# automatic_temp_control.net
KiCad netlist of a schematic drawn in EAGLE
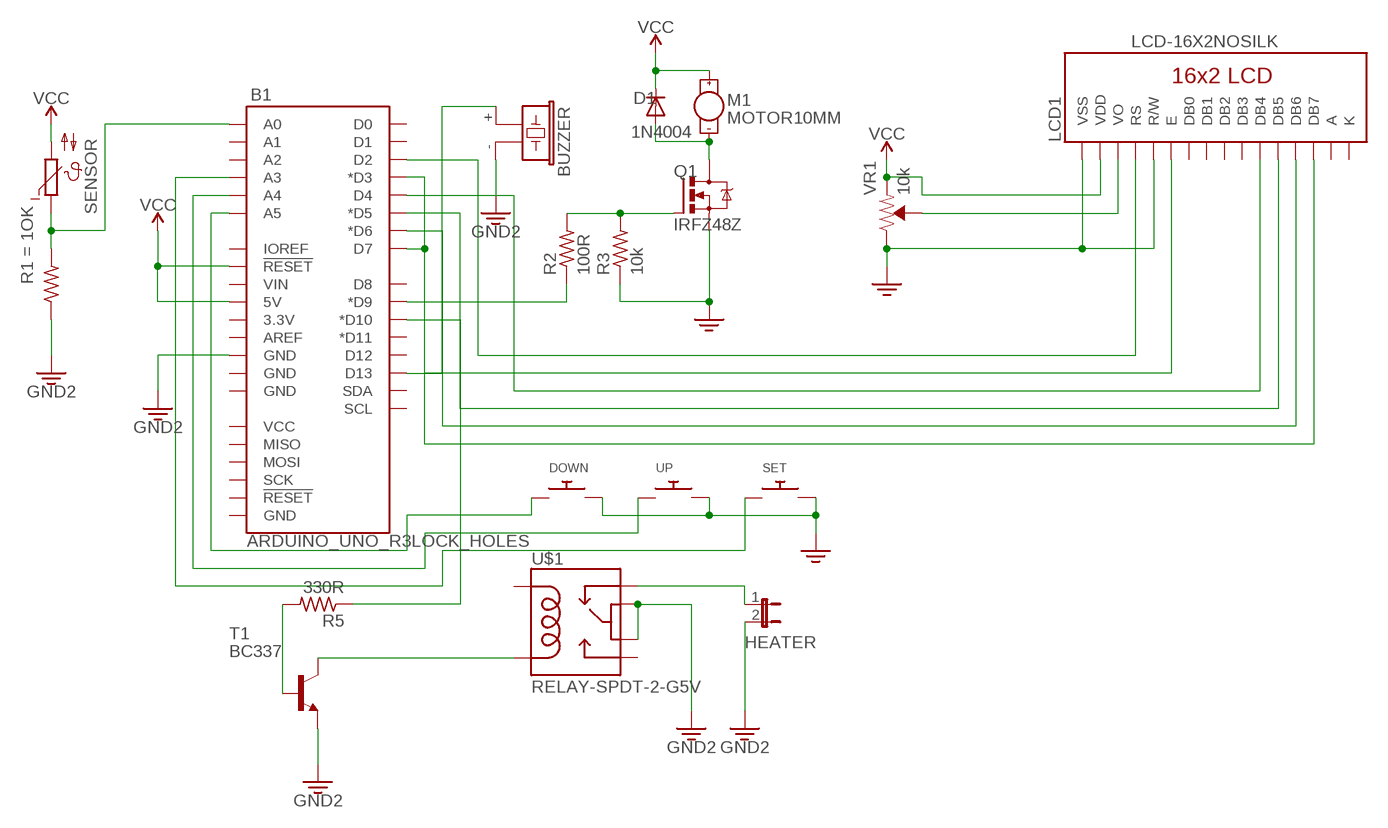
[diagram p0: schematic, sheet 1]

(export (version "E")
  (design (tool "Eeschema 10.0.6"))
  (components
    (comp (ref "B1")
      (value "ARDUINO_UNO_R3LOCK_HOLES")
      (footprint "eagle-import:ARDUINO_R3_LOCK_HOLES")
      (libsource (lib "eagle-import") (part "ARDUINO_UNO_R3LOCK_HOLES"))
    )
    (comp (ref "BUZZER")
      (value "F/CM04P")
      (footprint "eagle-import:F_CM04P")
      (libsource (lib "eagle-import") (part "F/CM04P"))
    )
    (comp (ref "D1")
      (value "1N4004")
      (footprint "eagle-import:DO41-10")
      (libsource (lib "eagle-import") (part "1N4004"))
    )
    (comp (ref "DOWN")
      (value "SWITCH_PUSHBUTTONEVQ-PE")
      (footprint "eagle-import:TACT_PANA-EVQ")
      (libsource (lib "eagle-import") (part "SWITCH_PUSHBUTTONEVQ-PE"))
    )
    (comp (ref "HEATER")
      (value "JP1E")
      (footprint "eagle-import:JP1")
      (libsource (lib "eagle-import") (part "JP1E"))
    )
    (comp (ref "LCD1")
      (value "LCD-16X2NOSILK")
      (footprint "eagle-import:LCD-16X2_NOSILK")
      (libsource (lib "eagle-import") (part "LCD-16X2NOSILK"))
    )
    (comp (ref "M1")
      (value "MOTOR10MM")
      (footprint "eagle-import:VIBE-MOTOR-10MM")
      (libsource (lib "eagle-import") (part "MOTOR10MM"))
    )
    (comp (ref "Q1")
      (value "IRFZ48Z")
      (footprint "eagle-import:TO220BH")
      (libsource (lib "eagle-import") (part "IRFZ48Z"))
    )
    (comp (ref "R2")
      (value "100R")
      (footprint "eagle-import:0204_7")
      (libsource (lib "eagle-import") (part "R-US_0204/7"))
    )
    (comp (ref "R3")
      (value "10k")
      (footprint "eagle-import:0204_7")
      (libsource (lib "eagle-import") (part "R-US_0204/7"))
    )
    (comp (ref "R4")
      (value "R-US_0204/7")
      (footprint "eagle-import:0204_7")
      (fields (field (name "R1") "1OK"))
      (libsource (lib "eagle-import") (part "R-US_0204/7"))
    )
    (comp (ref "R5")
      (value "330R")
      (footprint "eagle-import:0204_7")
      (libsource (lib "eagle-import") (part "R-US_0204/7"))
    )
    (comp (ref "SENSOR")
      (value "NTC640-9")
      (footprint "eagle-import:N640")
      (libsource (lib "eagle-import") (part "NTC640-9"))
    )
    (comp (ref "SET")
      (value "SWITCH_PUSHBUTTONEVQ-PE")
      (footprint "eagle-import:TACT_PANA-EVQ")
      (libsource (lib "eagle-import") (part "SWITCH_PUSHBUTTONEVQ-PE"))
    )
    (comp (ref "T1")
      (value "BC337")
      (footprint "eagle-import:TO92")
      (libsource (lib "eagle-import") (part "BC337"))
    )
    (comp (ref "U$1")
      (value "RELAY-SPDT-2-G5V")
      (footprint "eagle-import:RELAY-G5V")
      (libsource (lib "eagle-import") (part "RELAY-SPDT-2-G5V"))
    )
    (comp (ref "UP")
      (value "SWITCH_PUSHBUTTONEVQ-PE")
      (footprint "eagle-import:TACT_PANA-EVQ")
      (libsource (lib "eagle-import") (part "SWITCH_PUSHBUTTONEVQ-PE"))
    )
    (comp (ref "VR1")
      (value "10k")
      (footprint "eagle-import:TRIMPOT-PTH-3386U")
      (libsource (lib "eagle-import") (part "TRIMPOT-PTH-10MM-KNOB-1/2W-10%"))
    )
  )
  (nets
    (net (code "1") (name "/A") (class "Default")
      (node (ref "LCD1") (pin "15") (pinfunction "A_15") (pintype "power_in"))
    )
    (net (code "2") (name "/K") (class "Default")
      (node (ref "LCD1") (pin "16") (pinfunction "K_16") (pintype "power_in"))
    )
    (net (code "3") (name "GND2") (class "Default")
      (node (ref "B1") (pin "GND@4") (pinfunction "GND_GND@4") (pintype "bidirectional"))
      (node (ref "BUZZER") (pin "-") (pinfunction "2_-") (pintype "passive"))
      (node (ref "DOWN") (pin "P$2") (pinfunction "P$2_P$2") (pintype "passive"))
      (node (ref "HEATER") (pin "2") (pinfunction "2_2") (pintype "passive"))
      (node (ref "LCD1") (pin "1") (pinfunction "VSS_1") (pintype "power_in"))
      (node (ref "LCD1") (pin "5") (pinfunction "R/W_5") (pintype "input"))
      (node (ref "Q1") (pin "S") (pinfunction "S_S") (pintype "passive"))
      (node (ref "R3") (pin "1") (pinfunction "1_1") (pintype "passive"))
      (node (ref "R4") (pin "1") (pinfunction "1_1") (pintype "passive"))
      (node (ref "SET") (pin "P$2") (pinfunction "P$2_P$2") (pintype "passive"))
      (node (ref "T1") (pin "1") (pinfunction "E_1") (pintype "passive"))
      (node (ref "U$1") (pin "5") (pinfunction "5_5") (pintype "bidirectional"))
      (node (ref "U$1") (pin "6") (pinfunction "6_6") (pintype "bidirectional"))
      (node (ref "UP") (pin "P$2") (pinfunction "P$2_P$2") (pintype "passive"))
      (node (ref "VR1") (pin "3") (pinfunction "CW_3") (pintype "passive"))
    )
    (net (code "4") (name "Net-(B1-*D3)") (class "Default")
      (node (ref "B1") (pin "D3") (pinfunction "*D3_D3") (pintype "bidirectional"))
      (node (ref "B1") (pin "D7") (pinfunction "D7_D7") (pintype "bidirectional"))
      (node (ref "LCD1") (pin "14") (pinfunction "DB7_14") (pintype "bidirectional"))
      (node (ref "LCD1") (pin "6") (pinfunction "E_6") (pintype "input"))
    )
    (net (code "5") (name "Net-(B1-*D5)") (class "Default")
      (node (ref "B1") (pin "D5") (pinfunction "*D5_D5") (pintype "bidirectional"))
      (node (ref "LCD1") (pin "12") (pinfunction "DB5_12") (pintype "bidirectional"))
    )
    (net (code "6") (name "Net-(B1-*D6)") (class "Default")
      (node (ref "B1") (pin "D6") (pinfunction "*D6_D6") (pintype "bidirectional"))
      (node (ref "LCD1") (pin "13") (pinfunction "DB6_13") (pintype "bidirectional"))
    )
    (net (code "7") (name "Net-(B1-*D9)") (class "Default")
      (node (ref "B1") (pin "D9") (pinfunction "*D9_D9") (pintype "bidirectional"))
      (node (ref "R2") (pin "1") (pinfunction "1_1") (pintype "passive"))
    )
    (net (code "8") (name "Net-(B1-*D10)") (class "Default")
      (node (ref "B1") (pin "D10") (pinfunction "*D10_D10") (pintype "bidirectional"))
      (node (ref "R5") (pin "1") (pinfunction "1_1") (pintype "passive"))
    )
    (net (code "9") (name "Net-(B1-PadA0)") (class "Default")
      (node (ref "B1") (pin "A0") (pinfunction "A0_A0") (pintype "bidirectional"))
      (node (ref "R4") (pin "2") (pinfunction "2_2") (pintype "passive"))
      (node (ref "SENSOR") (pin "1") (pinfunction "1_1") (pintype "passive"))
    )
    (net (code "10") (name "Net-(B1-PadA3)") (class "Default")
      (node (ref "B1") (pin "A3") (pinfunction "A3_A3") (pintype "bidirectional"))
      (node (ref "SET") (pin "P$1") (pinfunction "P$1_P$1") (pintype "passive"))
    )
    (net (code "11") (name "Net-(B1-PadA4)") (class "Default")
      (node (ref "B1") (pin "A4") (pinfunction "A4_A4") (pintype "bidirectional"))
      (node (ref "UP") (pin "P$1") (pinfunction "P$1_P$1") (pintype "passive"))
    )
    (net (code "12") (name "Net-(B1-PadA5)") (class "Default")
      (node (ref "B1") (pin "A5") (pinfunction "A5_A5") (pintype "bidirectional"))
      (node (ref "DOWN") (pin "P$1") (pinfunction "P$1_P$1") (pintype "passive"))
    )
    (net (code "13") (name "Net-(BUZZER-1)") (class "Default")
      (node (ref "B1") (pin "D13") (pinfunction "D13_D13") (pintype "bidirectional"))
      (node (ref "BUZZER") (pin "+") (pinfunction "1_+") (pintype "passive"))
    )
    (net (code "14") (name "Net-(D1-PadA)") (class "Default")
      (node (ref "D1") (pin "A") (pinfunction "A_A") (pintype "passive"))
      (node (ref "M1") (pin "-") (pinfunction "-_-") (pintype "bidirectional"))
      (node (ref "Q1") (pin "D") (pinfunction "D_D") (pintype "passive"))
    )
    (net (code "15") (name "Net-(HEATER-Pad1)") (class "Default")
      (node (ref "HEATER") (pin "1") (pinfunction "1_1") (pintype "passive"))
      (node (ref "U$1") (pin "1") (pinfunction "1_1") (pintype "bidirectional"))
    )
    (net (code "16") (name "Net-(LCD1-DB4)") (class "Default")
      (node (ref "B1") (pin "D4") (pinfunction "D4_D4") (pintype "bidirectional"))
      (node (ref "LCD1") (pin "11") (pinfunction "DB4_11") (pintype "bidirectional"))
    )
    (net (code "17") (name "Net-(LCD1-RS)") (class "Default")
      (node (ref "B1") (pin "D2") (pinfunction "D2_D2") (pintype "bidirectional"))
      (node (ref "LCD1") (pin "4") (pinfunction "RS_4") (pintype "input"))
    )
    (net (code "18") (name "Net-(LCD1-VO)") (class "Default")
      (node (ref "LCD1") (pin "3") (pinfunction "VO_3") (pintype "bidirectional"))
      (node (ref "VR1") (pin "2") (pinfunction "WIPER_2") (pintype "passive"))
    )
    (net (code "19") (name "Net-(Q1-PadG)") (class "Default")
      (node (ref "Q1") (pin "G") (pinfunction "G_G") (pintype "passive"))
      (node (ref "R2") (pin "2") (pinfunction "2_2") (pintype "passive"))
      (node (ref "R3") (pin "2") (pinfunction "2_2") (pintype "passive"))
    )
    (net (code "20") (name "Net-(T1-B)") (class "Default")
      (node (ref "R5") (pin "2") (pinfunction "2_2") (pintype "passive"))
      (node (ref "T1") (pin "2") (pinfunction "B_2") (pintype "passive"))
    )
    (net (code "21") (name "Net-(T1-C)") (class "Default")
      (node (ref "T1") (pin "3") (pinfunction "C_3") (pintype "passive"))
      (node (ref "U$1") (pin "9") (pinfunction "9_9") (pintype "bidirectional"))
    )
    (net (code "22") (name "VCC") (class "Default")
      (node (ref "B1") (pin "5V") (pinfunction "5V_5V") (pintype "bidirectional"))
      (node (ref "B1") (pin "RESET@1") (pinfunction "~{RESET}_RESET@1") (pintype "bidirectional"))
      (node (ref "D1") (pin "C") (pinfunction "C_C") (pintype "passive"))
      (node (ref "LCD1") (pin "2") (pinfunction "VDD_2") (pintype "power_in"))
      (node (ref "M1") (pin "+") (pinfunction "+_+") (pintype "bidirectional"))
      (node (ref "SENSOR") (pin "2") (pinfunction "2_2") (pintype "passive"))
      (node (ref "VR1") (pin "1") (pinfunction "CCW_1") (pintype "passive"))
    )
    (net (code "23") (name "unconnected-(B1-*D11-PadD11)") (class "Default")
      (node (ref "B1") (pin "D11") (pinfunction "*D11_D11") (pintype "bidirectional"))
    )
    (net (code "24") (name "unconnected-(B1-GND-PadGND@1)") (class "Default")
      (node (ref "B1") (pin "GND@1") (pinfunction "GND_GND@1") (pintype "bidirectional"))
    )
    (net (code "25") (name "unconnected-(B1-GND-PadGND@2)") (class "Default")
      (node (ref "B1") (pin "GND@2") (pinfunction "GND_GND@2") (pintype "bidirectional"))
    )
    (net (code "26") (name "unconnected-(B1-GND-PadGND@3)") (class "Default")
      (node (ref "B1") (pin "GND@3") (pinfunction "GND_GND@3") (pintype "bidirectional"))
    )
    (net (code "27") (name "unconnected-(B1-Pad3.3V)") (class "Default")
      (node (ref "B1") (pin "3.3V") (pinfunction "3.3V_3.3V") (pintype "bidirectional"))
    )
    (net (code "28") (name "unconnected-(B1-PadA1)") (class "Default")
      (node (ref "B1") (pin "A1") (pinfunction "A1_A1") (pintype "bidirectional"))
    )
    (net (code "29") (name "unconnected-(B1-PadA2)") (class "Default")
      (node (ref "B1") (pin "A2") (pinfunction "A2_A2") (pintype "bidirectional"))
    )
    (net (code "30") (name "unconnected-(B1-PadAREF)") (class "Default")
      (node (ref "B1") (pin "AREF") (pinfunction "AREF_AREF") (pintype "bidirectional"))
    )
    (net (code "31") (name "unconnected-(B1-PadD0)") (class "Default")
      (node (ref "B1") (pin "D0") (pinfunction "D0_D0") (pintype "bidirectional"))
    )
    (net (code "32") (name "unconnected-(B1-PadD1)") (class "Default")
      (node (ref "B1") (pin "D1") (pinfunction "D1_D1") (pintype "bidirectional"))
    )
    (net (code "33") (name "unconnected-(B1-PadD8)") (class "Default")
      (node (ref "B1") (pin "D8") (pinfunction "D8_D8") (pintype "bidirectional"))
    )
    (net (code "34") (name "unconnected-(B1-PadD12)") (class "Default")
      (node (ref "B1") (pin "D12") (pinfunction "D12_D12") (pintype "bidirectional"))
    )
    (net (code "35") (name "unconnected-(B1-PadIOREF)") (class "Default")
      (node (ref "B1") (pin "IOREF") (pinfunction "IOREF_IOREF") (pintype "bidirectional"))
    )
    (net (code "36") (name "unconnected-(B1-PadMISO)") (class "Default")
      (node (ref "B1") (pin "MISO") (pinfunction "MISO_MISO") (pintype "bidirectional"))
    )
    (net (code "37") (name "unconnected-(B1-PadMOSI)") (class "Default")
      (node (ref "B1") (pin "MOSI") (pinfunction "MOSI_MOSI") (pintype "bidirectional"))
    )
    (net (code "38") (name "unconnected-(B1-PadSCK)") (class "Default")
      (node (ref "B1") (pin "SCK") (pinfunction "SCK_SCK") (pintype "bidirectional"))
    )
    (net (code "39") (name "unconnected-(B1-PadSCL)") (class "Default")
      (node (ref "B1") (pin "SCL") (pinfunction "SCL_SCL") (pintype "bidirectional"))
    )
    (net (code "40") (name "unconnected-(B1-PadSDA)") (class "Default")
      (node (ref "B1") (pin "SDA") (pinfunction "SDA_SDA") (pintype "bidirectional"))
    )
    (net (code "41") (name "unconnected-(B1-PadVCC)") (class "Default")
      (node (ref "B1") (pin "VCC") (pinfunction "VCC_VCC") (pintype "bidirectional"))
    )
    (net (code "42") (name "unconnected-(B1-PadVIN)") (class "Default")
      (node (ref "B1") (pin "VIN") (pinfunction "VIN_VIN") (pintype "bidirectional"))
    )
    (net (code "43") (name "unconnected-(B1-~{RESET}-PadRESET@2)") (class "Default")
      (node (ref "B1") (pin "RESET@2") (pinfunction "~{RESET}_RESET@2") (pintype "bidirectional"))
    )
    (net (code "44") (name "unconnected-(LCD1-DB0-Pad7)") (class "Default")
      (node (ref "LCD1") (pin "7") (pinfunction "DB0_7") (pintype "bidirectional"))
    )
    (net (code "45") (name "unconnected-(LCD1-DB1-Pad8)") (class "Default")
      (node (ref "LCD1") (pin "8") (pinfunction "DB1_8") (pintype "bidirectional"))
    )
    (net (code "46") (name "unconnected-(LCD1-DB2-Pad9)") (class "Default")
      (node (ref "LCD1") (pin "9") (pinfunction "DB2_9") (pintype "bidirectional"))
    )
    (net (code "47") (name "unconnected-(LCD1-DB3-Pad10)") (class "Default")
      (node (ref "LCD1") (pin "10") (pinfunction "DB3_10") (pintype "bidirectional"))
    )
    (net (code "48") (name "unconnected-(U$1-Pad2)") (class "Default")
      (node (ref "U$1") (pin "2") (pinfunction "2_2") (pintype "bidirectional"))
    )
    (net (code "49") (name "unconnected-(U$1-Pad10)") (class "Default")
      (node (ref "U$1") (pin "10") (pinfunction "10_10") (pintype "bidirectional"))
    )
  )
)
